# SCH_trail_2024-05-24.net
KiCad netlist of a schematic drawn in EasyEDA
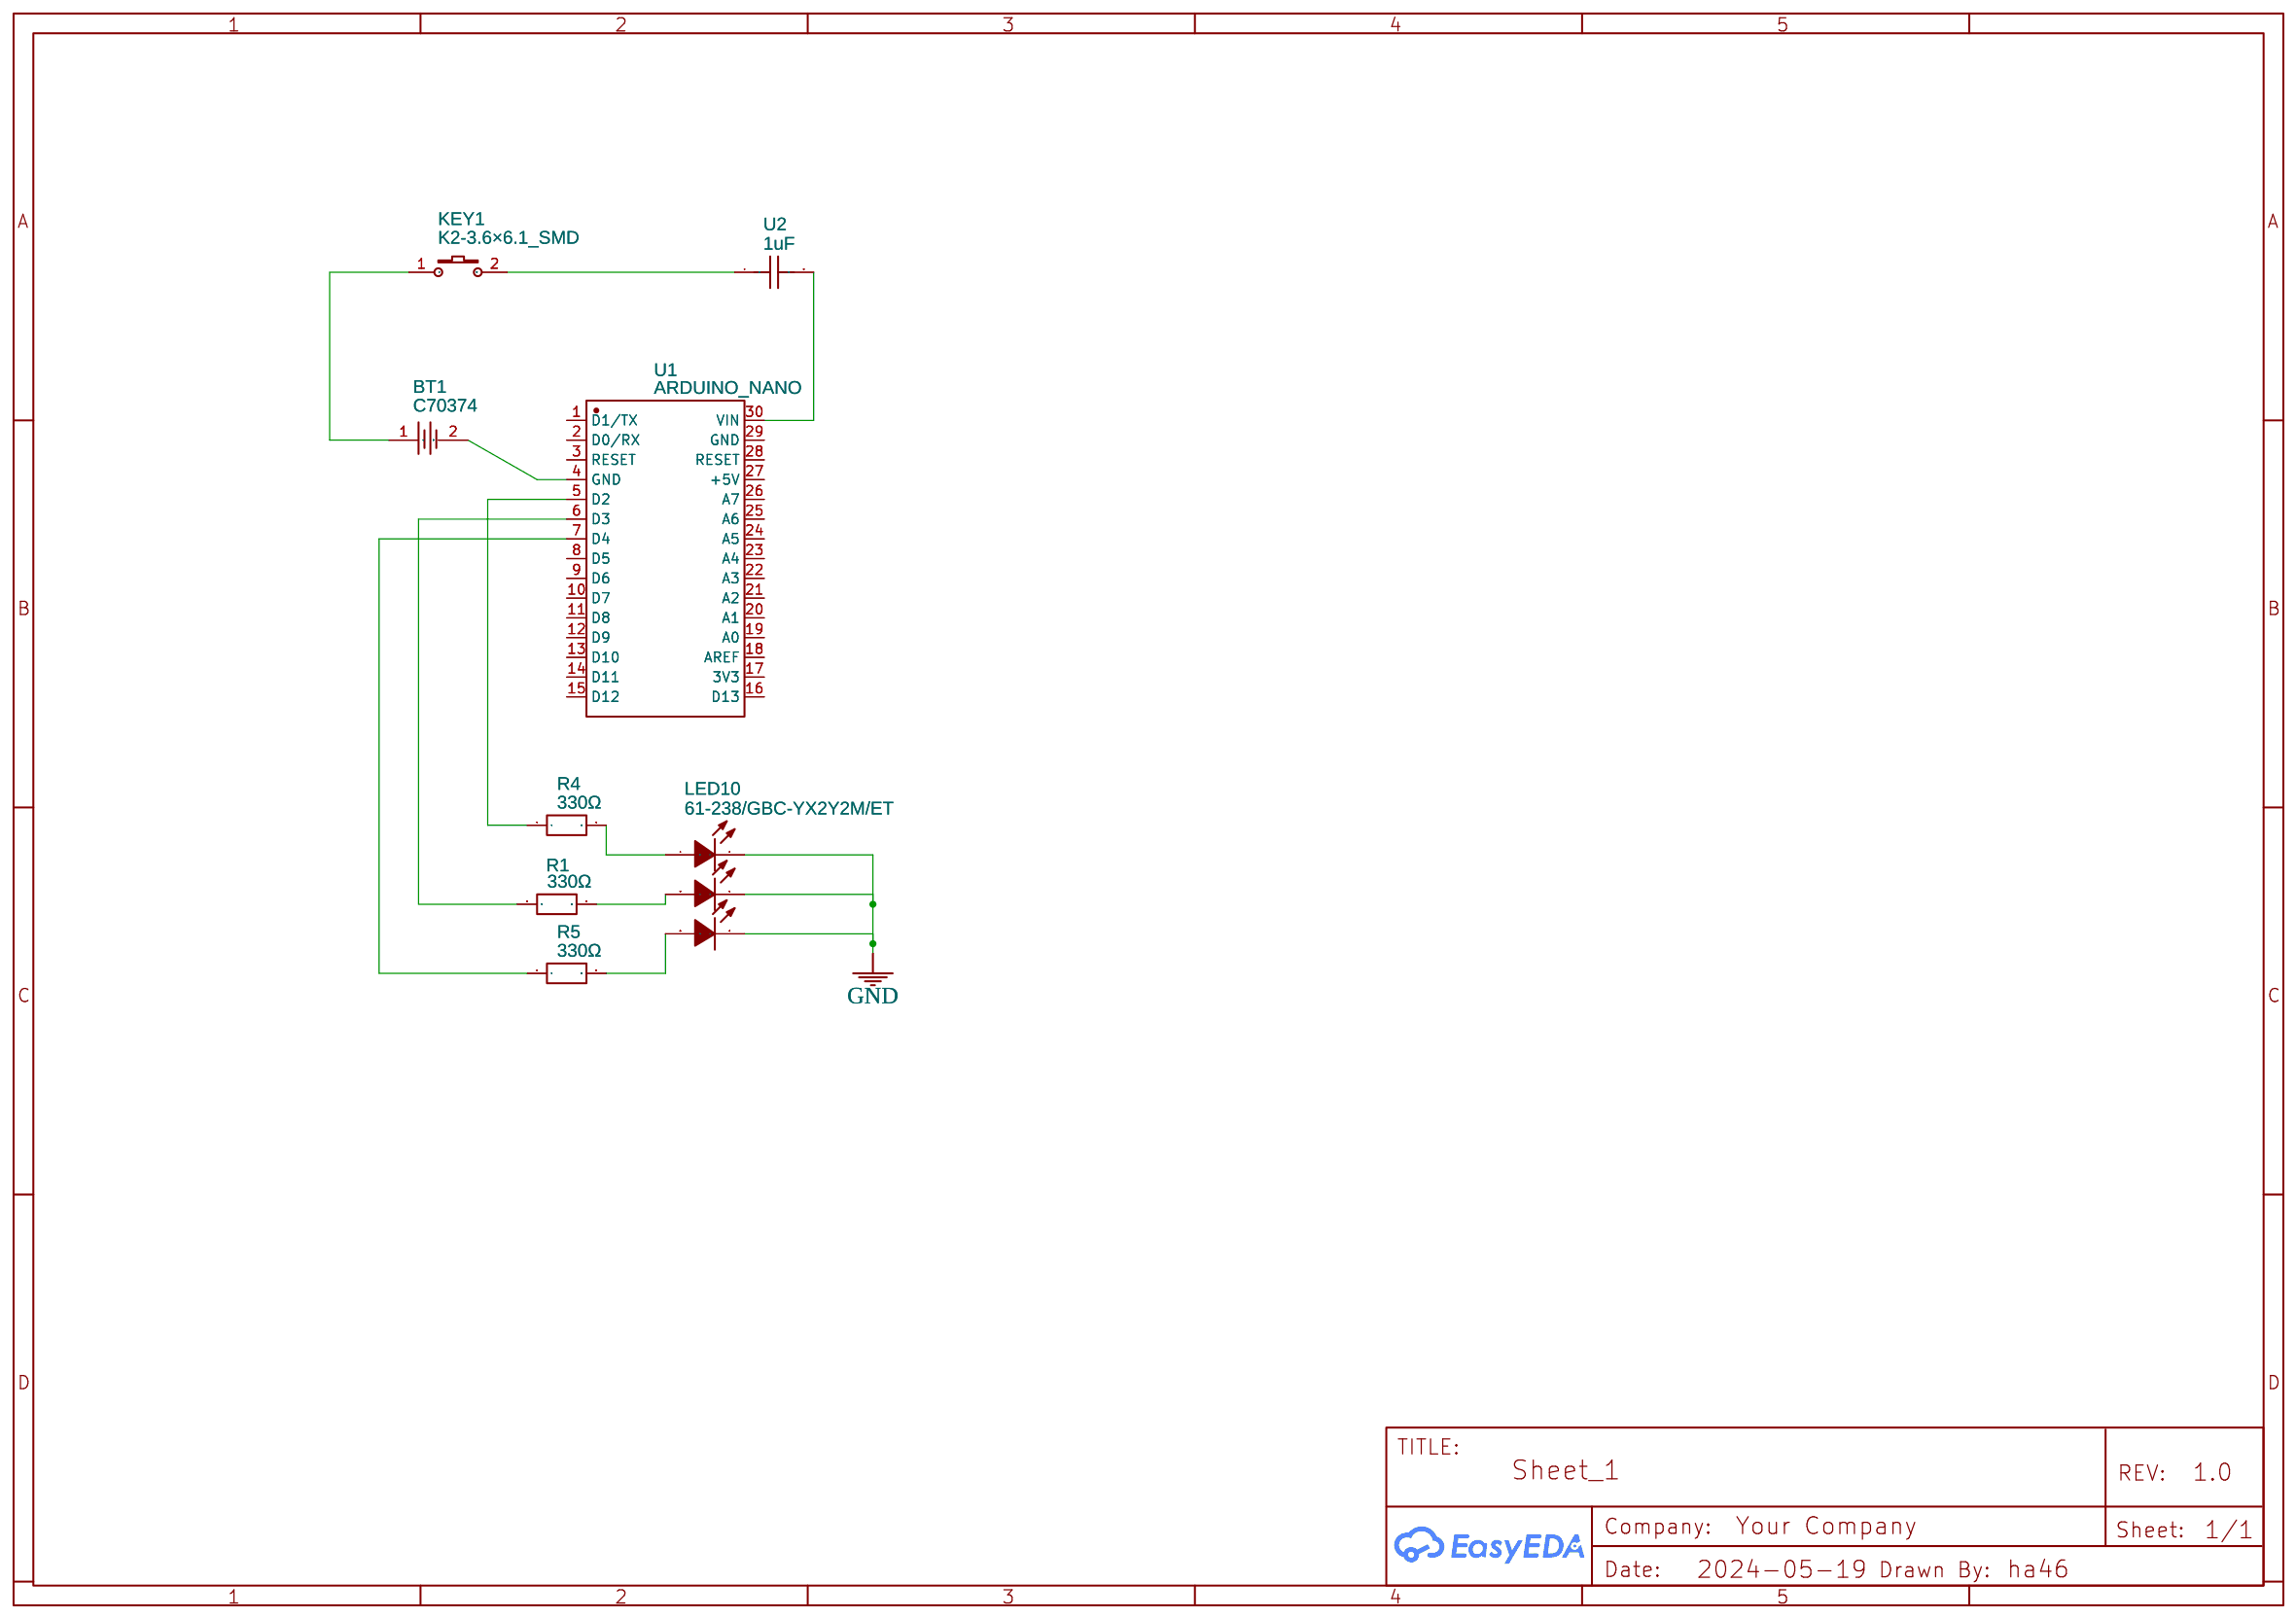
[diagram p0: schematic sheet]

(export (version "E")
  (design (tool "Eeschema 10.0.6"))
  (components
    (comp (ref "BT1")
      (value "C70374")
      (fields (field (name "Manufacturer") "Q&J"))
      (libsource (lib "") (part "C70374"))
    )
    (comp (ref "KEY1")
      (value "K2-3.6×6.1_SMD")
      (fields (field (name "Manufacturer Part") "K2-1107ST-A4SW-06"))
      (libsource (lib "") (part "K2-3.6×6.1_SMD"))
    )
    (comp (ref "LED10")
      (value "61-238/GBC-YX2Y2M/ET")
      (fields (field (name "Manufacturer") "EVERLIGHT(亿光)"))
      (libsource (lib "") (part "61-238/GBC-YX2Y2M/ET"))
    )
    (comp (ref "R1")
      (value "330Ω")
      (fields
        (field (name "Manufacturer Part") "CR0805J330RP05Z")
        (field (name "Manufacturer") "EVER OHMS(天二科技)")
      )
      (libsource (lib "") (part "CR0805J330RP05Z"))
    )
    (comp (ref "R4")
      (value "330Ω")
      (fields
        (field (name "Manufacturer Part") "CR0805J330RP05Z")
        (field (name "Manufacturer") "EVER OHMS(天二科技)")
      )
      (libsource (lib "") (part "CR0805J330RP05Z"))
    )
    (comp (ref "R5")
      (value "330Ω")
      (fields
        (field (name "Manufacturer Part") "CR0805J330RP05Z")
        (field (name "Manufacturer") "EVER OHMS(天二科技)")
      )
      (libsource (lib "") (part "CR0805J330RP05Z"))
    )
    (comp (ref "U1") (value "ARDUINO_NANO") (libsource (lib "") (part "ARDUINO_NANO")))
    (comp (ref "U2")
      (value "1uF")
      (fields
        (field (name "Manufacturer Part") "CS1608Y5V105Z160NRB")
        (field (name "Manufacturer") "SAMWHA(三和)")
      )
      (libsource (lib "") (part "CS1608Y5V105Z160NRB"))
    )
  )
  (nets
    (net (code "1") (name "GND") (class "Default")
      (node (ref "LED10") (pin "1") (pinfunction "-_1") (pintype "unspecified"))
      (node (ref "LED10") (pin "2") (pinfunction "-_2") (pintype "unspecified"))
      (node (ref "LED10") (pin "3") (pinfunction "-_3") (pintype "unspecified"))
    )
    (net (code "2") (name "Net-(BT1-Pad1)") (class "Default")
      (node (ref "BT1") (pin "1") (pinfunction "1_1") (pintype "input"))
      (node (ref "KEY1") (pin "1") (pinfunction "1_1") (pintype "unspecified"))
    )
    (net (code "3") (name "Net-(BT1-Pad2)") (class "Default")
      (node (ref "BT1") (pin "2") (pinfunction "2_2") (pintype "input"))
      (node (ref "U1") (pin "4") (pinfunction "GND_4") (pintype "unspecified"))
    )
    (net (code "4") (name "Net-(KEY1-Pad2)") (class "Default")
      (node (ref "KEY1") (pin "2") (pinfunction "2_2") (pintype "unspecified"))
      (node (ref "U2") (pin "1") (pinfunction "1_1") (pintype "unspecified"))
    )
    (net (code "5") (name "Net-(LED10-+-Pad4)") (class "Default")
      (node (ref "LED10") (pin "4") (pinfunction "+_4") (pintype "unspecified"))
      (node (ref "R4") (pin "2") (pinfunction "2_2") (pintype "unspecified"))
    )
    (net (code "6") (name "Net-(LED10-+-Pad5)") (class "Default")
      (node (ref "LED10") (pin "5") (pinfunction "+_5") (pintype "unspecified"))
      (node (ref "R1") (pin "2") (pinfunction "2_2") (pintype "unspecified"))
    )
    (net (code "7") (name "Net-(LED10-+-Pad6)") (class "Default")
      (node (ref "LED10") (pin "6") (pinfunction "+_6") (pintype "unspecified"))
      (node (ref "R5") (pin "2") (pinfunction "2_2") (pintype "unspecified"))
    )
    (net (code "8") (name "Net-(U1-D2)") (class "Default")
      (node (ref "R4") (pin "1") (pinfunction "1_1") (pintype "unspecified"))
      (node (ref "U1") (pin "5") (pinfunction "D2_5") (pintype "unspecified"))
    )
    (net (code "9") (name "Net-(U1-D3)") (class "Default")
      (node (ref "R1") (pin "1") (pinfunction "1_1") (pintype "unspecified"))
      (node (ref "U1") (pin "6") (pinfunction "D3_6") (pintype "unspecified"))
    )
    (net (code "10") (name "Net-(U1-D4)") (class "Default")
      (node (ref "R5") (pin "1") (pinfunction "1_1") (pintype "unspecified"))
      (node (ref "U1") (pin "7") (pinfunction "D4_7") (pintype "unspecified"))
    )
    (net (code "11") (name "Net-(U1-VIN)") (class "Default")
      (node (ref "U1") (pin "30") (pinfunction "VIN_30") (pintype "unspecified"))
      (node (ref "U2") (pin "2") (pinfunction "2_2") (pintype "unspecified"))
    )
    (net (code "12") (name "unconnected-(U1-+5V-Pad27)") (class "Default")
      (node (ref "U1") (pin "27") (pinfunction "+5V_27") (pintype "unspecified"))
    )
    (net (code "13") (name "unconnected-(U1-3V3-Pad17)") (class "Default")
      (node (ref "U1") (pin "17") (pinfunction "3V3_17") (pintype "unspecified"))
    )
    (net (code "14") (name "unconnected-(U1-A0-Pad19)") (class "Default")
      (node (ref "U1") (pin "19") (pinfunction "A0_19") (pintype "unspecified"))
    )
    (net (code "15") (name "unconnected-(U1-A1-Pad20)") (class "Default")
      (node (ref "U1") (pin "20") (pinfunction "A1_20") (pintype "unspecified"))
    )
    (net (code "16") (name "unconnected-(U1-A2-Pad21)") (class "Default")
      (node (ref "U1") (pin "21") (pinfunction "A2_21") (pintype "unspecified"))
    )
    (net (code "17") (name "unconnected-(U1-A3-Pad22)") (class "Default")
      (node (ref "U1") (pin "22") (pinfunction "A3_22") (pintype "unspecified"))
    )
    (net (code "18") (name "unconnected-(U1-A4-Pad23)") (class "Default")
      (node (ref "U1") (pin "23") (pinfunction "A4_23") (pintype "unspecified"))
    )
    (net (code "19") (name "unconnected-(U1-A5-Pad24)") (class "Default")
      (node (ref "U1") (pin "24") (pinfunction "A5_24") (pintype "unspecified"))
    )
    (net (code "20") (name "unconnected-(U1-A6-Pad25)") (class "Default")
      (node (ref "U1") (pin "25") (pinfunction "A6_25") (pintype "unspecified"))
    )
    (net (code "21") (name "unconnected-(U1-A7-Pad26)") (class "Default")
      (node (ref "U1") (pin "26") (pinfunction "A7_26") (pintype "unspecified"))
    )
    (net (code "22") (name "unconnected-(U1-AREF-Pad18)") (class "Default")
      (node (ref "U1") (pin "18") (pinfunction "AREF_18") (pintype "unspecified"))
    )
    (net (code "23") (name "unconnected-(U1-D0{slash}RX-Pad2)") (class "Default")
      (node (ref "U1") (pin "2") (pinfunction "D0/RX_2") (pintype "unspecified"))
    )
    (net (code "24") (name "unconnected-(U1-D1{slash}TX-Pad1)") (class "Default")
      (node (ref "U1") (pin "1") (pinfunction "D1/TX_1") (pintype "unspecified"))
    )
    (net (code "25") (name "unconnected-(U1-D5-Pad8)") (class "Default")
      (node (ref "U1") (pin "8") (pinfunction "D5_8") (pintype "unspecified"))
    )
    (net (code "26") (name "unconnected-(U1-D6-Pad9)") (class "Default")
      (node (ref "U1") (pin "9") (pinfunction "D6_9") (pintype "unspecified"))
    )
    (net (code "27") (name "unconnected-(U1-D7-Pad10)") (class "Default")
      (node (ref "U1") (pin "10") (pinfunction "D7_10") (pintype "unspecified"))
    )
    (net (code "28") (name "unconnected-(U1-D8-Pad11)") (class "Default")
      (node (ref "U1") (pin "11") (pinfunction "D8_11") (pintype "unspecified"))
    )
    (net (code "29") (name "unconnected-(U1-D9-Pad12)") (class "Default")
      (node (ref "U1") (pin "12") (pinfunction "D9_12") (pintype "unspecified"))
    )
    (net (code "30") (name "unconnected-(U1-D10-Pad13)") (class "Default")
      (node (ref "U1") (pin "13") (pinfunction "D10_13") (pintype "unspecified"))
    )
    (net (code "31") (name "unconnected-(U1-D11-Pad14)") (class "Default")
      (node (ref "U1") (pin "14") (pinfunction "D11_14") (pintype "unspecified"))
    )
    (net (code "32") (name "unconnected-(U1-D12-Pad15)") (class "Default")
      (node (ref "U1") (pin "15") (pinfunction "D12_15") (pintype "unspecified"))
    )
    (net (code "33") (name "unconnected-(U1-D13-Pad16)") (class "Default")
      (node (ref "U1") (pin "16") (pinfunction "D13_16") (pintype "unspecified"))
    )
    (net (code "34") (name "unconnected-(U1-GND-Pad29)") (class "Default")
      (node (ref "U1") (pin "29") (pinfunction "GND_29") (pintype "unspecified"))
    )
    (net (code "35") (name "unconnected-(U1-RESET-Pad3)") (class "Default")
      (node (ref "U1") (pin "3") (pinfunction "RESET_3") (pintype "unspecified"))
    )
    (net (code "36") (name "unconnected-(U1-RESET-Pad28)") (class "Default")
      (node (ref "U1") (pin "28") (pinfunction "RESET_28") (pintype "unspecified"))
    )
  )
)
